# Sheet1.net
KiCad netlist of a schematic drawn in Altium Designer
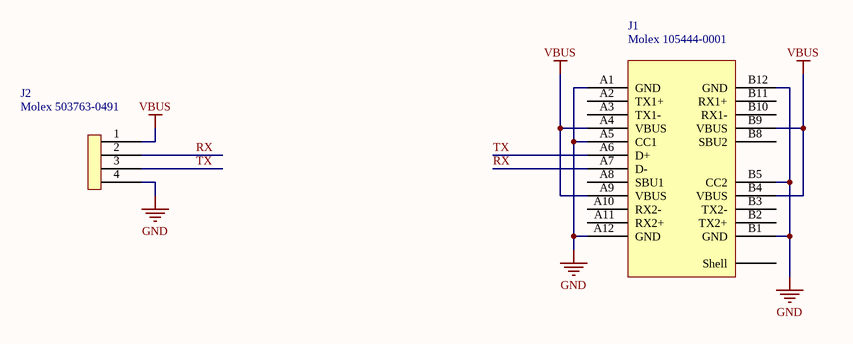
[diagram p0: Sheet1.SchDoc]

(export (version "E")
  (design (tool "Eeschema 10.0.6"))
  (components
    (comp (ref "J1")
      (value "Molex 105444-0001")
      (footprint "Molex 105444-0001")
      (libsource (lib "x-io") (part "USB-C Plug"))
    )
    (comp (ref "J2")
      (value "Molex 503763-0491")
      (footprint "Molex 503763-0491")
      (libsource (lib "x-io") (part "Molex 503763-0491"))
    )
  )
  (nets
    (net (code "1") (name "/RX") (class "Default")
      (node (ref "J1") (pin "A7") (pinfunction "D-_A7") (pintype "passive"))
      (node (ref "J2") (pin "2") (pinfunction "2_2") (pintype "passive"))
    )
    (net (code "2") (name "/TX") (class "Default")
      (node (ref "J1") (pin "A6") (pinfunction "D+_A6") (pintype "passive"))
      (node (ref "J2") (pin "3") (pinfunction "3_3") (pintype "passive"))
    )
    (net (code "3") (name "GND") (class "Default")
      (node (ref "J1") (pin "A1") (pinfunction "GND_A1") (pintype "passive"))
      (node (ref "J1") (pin "A12") (pinfunction "GND_A12") (pintype "passive"))
      (node (ref "J1") (pin "A5") (pinfunction "CC1_A5") (pintype "passive"))
      (node (ref "J1") (pin "B1") (pinfunction "GND_B1") (pintype "passive"))
      (node (ref "J1") (pin "B12") (pinfunction "GND_B12") (pintype "passive"))
      (node (ref "J1") (pin "B5") (pinfunction "CC2_B5") (pintype "passive"))
      (node (ref "J2") (pin "4") (pinfunction "4_4") (pintype "passive"))
    )
    (net (code "4") (name "VBUS") (class "Default")
      (node (ref "J1") (pin "A4") (pinfunction "VBUS_A4") (pintype "passive"))
      (node (ref "J1") (pin "A9") (pinfunction "VBUS_A9") (pintype "passive"))
      (node (ref "J1") (pin "B4") (pinfunction "VBUS_B4") (pintype "passive"))
      (node (ref "J1") (pin "B9") (pinfunction "VBUS_B9") (pintype "passive"))
      (node (ref "J2") (pin "1") (pinfunction "1_1") (pintype "passive"))
    )
    (net (code "5") (name "unconnected-(J1-PadShell)") (class "Default")
      (node (ref "J1") (pin "Shell") (pinfunction "Shell_Shell") (pintype "passive"))
    )
    (net (code "6") (name "unconnected-(J1-RX1+-PadB11)") (class "Default")
      (node (ref "J1") (pin "B11") (pinfunction "RX1+_B11") (pintype "passive"))
    )
    (net (code "7") (name "unconnected-(J1-RX1--PadB10)") (class "Default")
      (node (ref "J1") (pin "B10") (pinfunction "RX1-_B10") (pintype "passive"))
    )
    (net (code "8") (name "unconnected-(J1-RX2+-PadA11)") (class "Default")
      (node (ref "J1") (pin "A11") (pinfunction "RX2+_A11") (pintype "passive"))
    )
    (net (code "9") (name "unconnected-(J1-RX2--PadA10)") (class "Default")
      (node (ref "J1") (pin "A10") (pinfunction "RX2-_A10") (pintype "passive"))
    )
    (net (code "10") (name "unconnected-(J1-SBU1-PadA8)") (class "Default")
      (node (ref "J1") (pin "A8") (pinfunction "SBU1_A8") (pintype "passive"))
    )
    (net (code "11") (name "unconnected-(J1-SBU2-PadB8)") (class "Default")
      (node (ref "J1") (pin "B8") (pinfunction "SBU2_B8") (pintype "passive"))
    )
    (net (code "12") (name "unconnected-(J1-TX1+-PadA2)") (class "Default")
      (node (ref "J1") (pin "A2") (pinfunction "TX1+_A2") (pintype "passive"))
    )
    (net (code "13") (name "unconnected-(J1-TX1--PadA3)") (class "Default")
      (node (ref "J1") (pin "A3") (pinfunction "TX1-_A3") (pintype "passive"))
    )
    (net (code "14") (name "unconnected-(J1-TX2+-PadB2)") (class "Default")
      (node (ref "J1") (pin "B2") (pinfunction "TX2+_B2") (pintype "passive"))
    )
    (net (code "15") (name "unconnected-(J1-TX2--PadB3)") (class "Default")
      (node (ref "J1") (pin "B3") (pinfunction "TX2-_B3") (pintype "passive"))
    )
  )
)
